# MotorControl.net
KiCad netlist of a schematic drawn in EAGLE
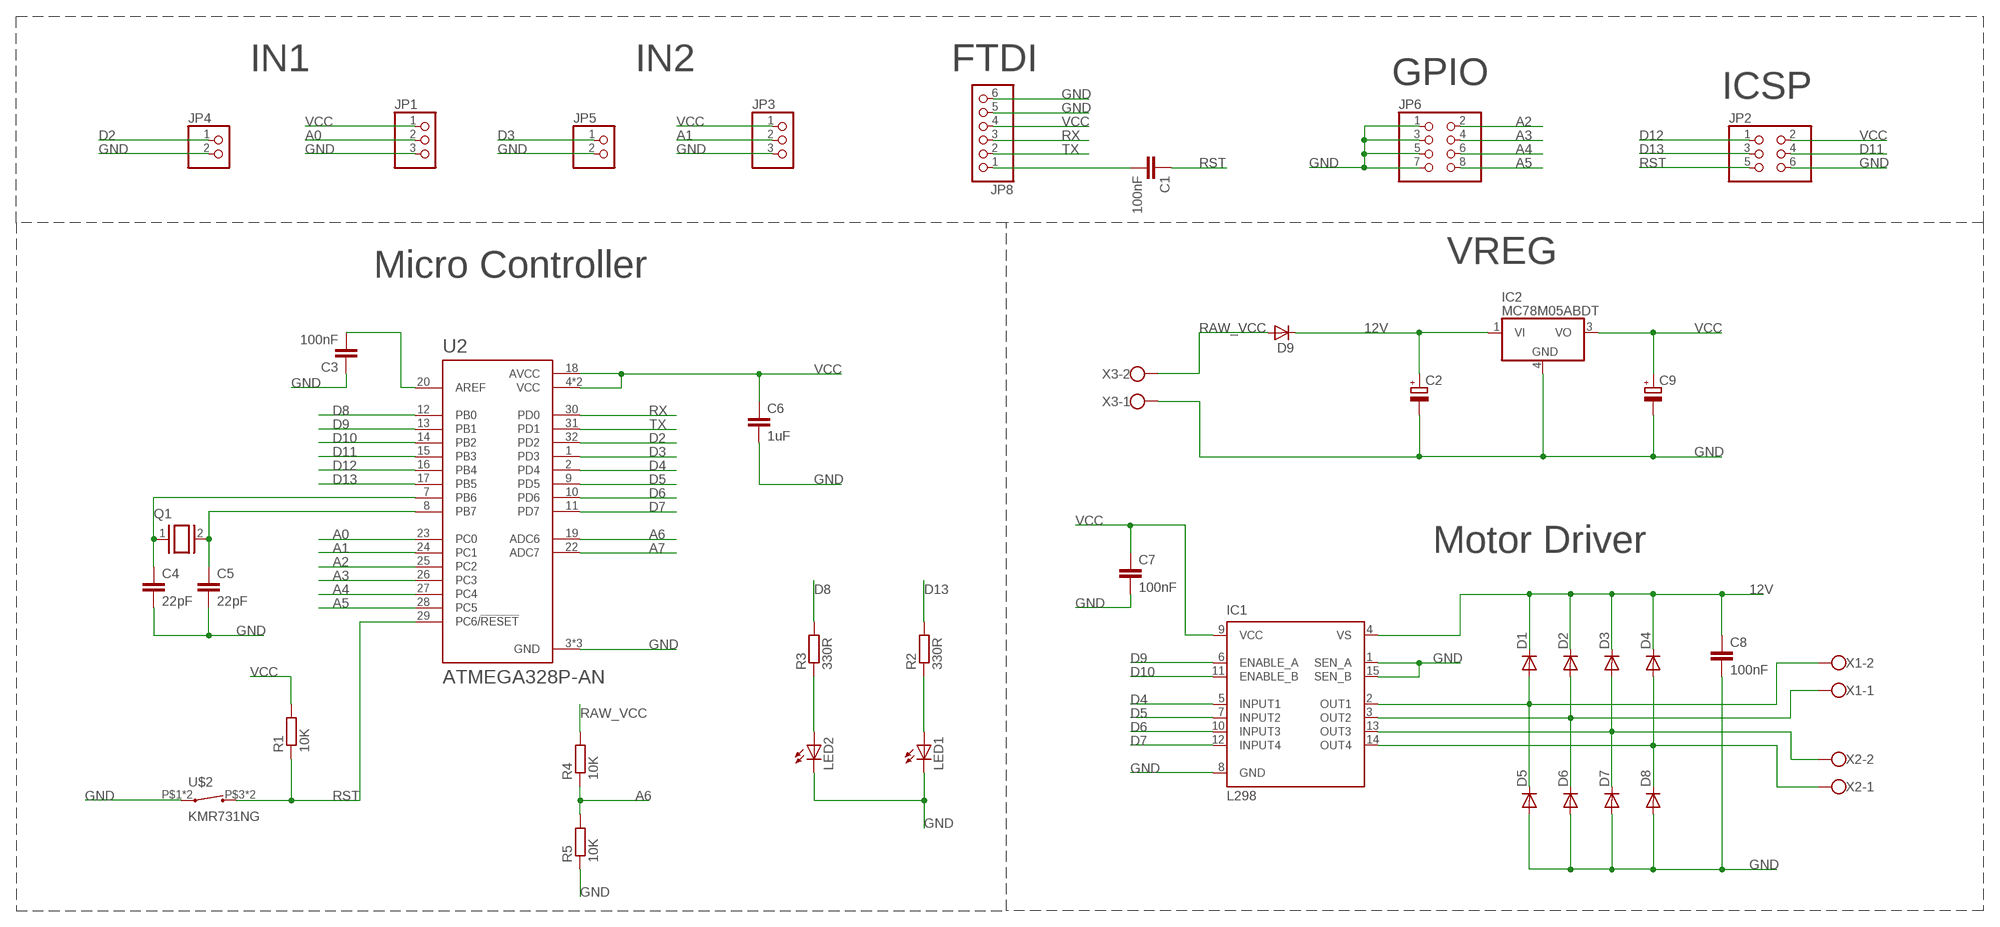
[diagram p0: schematic, sheet 1]

(export (version "E")
  (design (tool "Eeschema 10.0.6"))
  (components
    (comp (ref "C1")
      (value "100nF")
      (footprint "eagle-import:C1206")
      (libsource (lib "eagle-import") (part "CC1206"))
    )
    (comp (ref "C2")
      (value "CPOL-EU140CLH-0810")
      (footprint "eagle-import:140CLH-0810")
      (libsource (lib "eagle-import") (part "CPOL-EU140CLH-0810"))
    )
    (comp (ref "C3")
      (value "100nF")
      (footprint "eagle-import:C1206")
      (libsource (lib "eagle-import") (part "CC1206"))
    )
    (comp (ref "C4")
      (value "22pF")
      (footprint "eagle-import:C1206")
      (libsource (lib "eagle-import") (part "CC1206"))
    )
    (comp (ref "C5")
      (value "22pF")
      (footprint "eagle-import:C1206")
      (libsource (lib "eagle-import") (part "CC1206"))
    )
    (comp (ref "C6")
      (value "1uF")
      (footprint "eagle-import:C1206")
      (libsource (lib "eagle-import") (part "CC1206"))
    )
    (comp (ref "C7")
      (value "100nF")
      (footprint "eagle-import:C1206")
      (libsource (lib "eagle-import") (part "CC1206"))
    )
    (comp (ref "C8")
      (value "100nF")
      (footprint "eagle-import:C1206")
      (libsource (lib "eagle-import") (part "CC1206"))
    )
    (comp (ref "C9")
      (value "CPOL-EU140CLH-0810")
      (footprint "eagle-import:140CLH-0810")
      (libsource (lib "eagle-import") (part "CPOL-EU140CLH-0810"))
    )
    (comp (ref "D1")
      (value "DIODE-DO214AC")
      (footprint "eagle-import:DO214AC")
      (libsource (lib "eagle-import") (part "DIODE-DO214AC"))
    )
    (comp (ref "D2")
      (value "DIODE-DO214AC")
      (footprint "eagle-import:DO214AC")
      (libsource (lib "eagle-import") (part "DIODE-DO214AC"))
    )
    (comp (ref "D3")
      (value "DIODE-DO214AC")
      (footprint "eagle-import:DO214AC")
      (libsource (lib "eagle-import") (part "DIODE-DO214AC"))
    )
    (comp (ref "D4")
      (value "DIODE-DO214AC")
      (footprint "eagle-import:DO214AC")
      (libsource (lib "eagle-import") (part "DIODE-DO214AC"))
    )
    (comp (ref "D5")
      (value "DIODE-DO214AC")
      (footprint "eagle-import:DO214AC")
      (libsource (lib "eagle-import") (part "DIODE-DO214AC"))
    )
    (comp (ref "D6")
      (value "DIODE-DO214AC")
      (footprint "eagle-import:DO214AC")
      (libsource (lib "eagle-import") (part "DIODE-DO214AC"))
    )
    (comp (ref "D7")
      (value "DIODE-DO214AC")
      (footprint "eagle-import:DO214AC")
      (libsource (lib "eagle-import") (part "DIODE-DO214AC"))
    )
    (comp (ref "D8")
      (value "DIODE-DO214AC")
      (footprint "eagle-import:DO214AC")
      (libsource (lib "eagle-import") (part "DIODE-DO214AC"))
    )
    (comp (ref "D9")
      (value "DIODE_E-SMC")
      (footprint "eagle-import:DIODE_SMC")
      (libsource (lib "eagle-import") (part "DIODE_E-SMC"))
    )
    (comp (ref "IC1")
      (value "L298")
      (footprint "eagle-import:MULTIWATT-15")
      (fields (field (name "MPN") "L298N"))
      (libsource (lib "eagle-import") (part "L298"))
    )
    (comp (ref "IC2")
      (value "MC78M05ABDT")
      (footprint "eagle-import:DPACK_3")
      (libsource (lib "eagle-import") (part "MC78M05ABDT"))
    )
    (comp (ref "JP1")
      (value "PINHD-1X3")
      (footprint "eagle-import:1X03")
      (libsource (lib "eagle-import") (part "PINHD-1X3"))
    )
    (comp (ref "JP2")
      (value "PINHD-2X3")
      (footprint "eagle-import:2X03")
      (libsource (lib "eagle-import") (part "PINHD-2X3"))
    )
    (comp (ref "JP3")
      (value "PINHD-1X3")
      (footprint "eagle-import:1X03")
      (libsource (lib "eagle-import") (part "PINHD-1X3"))
    )
    (comp (ref "JP4")
      (value "PINHD-1X2")
      (footprint "eagle-import:1X02")
      (libsource (lib "eagle-import") (part "PINHD-1X2"))
    )
    (comp (ref "JP5")
      (value "PINHD-1X2")
      (footprint "eagle-import:1X02")
      (libsource (lib "eagle-import") (part "PINHD-1X2"))
    )
    (comp (ref "JP6")
      (value "PINHD-2X4")
      (footprint "eagle-import:2X04")
      (libsource (lib "eagle-import") (part "PINHD-2X4"))
    )
    (comp (ref "JP8")
      (value "PINHD-1X6")
      (footprint "eagle-import:1X06")
      (libsource (lib "eagle-import") (part "PINHD-1X6"))
    )
    (comp (ref "LED1")
      (value "LED_ESML0603")
      (footprint "eagle-import:LED_SML0603")
      (libsource (lib "eagle-import") (part "LED_ESML0603"))
    )
    (comp (ref "LED2")
      (value "LED3MM")
      (footprint "eagle-import:LED3MM")
      (libsource (lib "eagle-import") (part "LED3MM"))
    )
    (comp (ref "Q1")
      (value "XTAL/S")
      (footprint "eagle-import:QS")
      (libsource (lib "eagle-import") (part "XTAL/S"))
    )
    (comp (ref "R1")
      (value "10K")
      (footprint "eagle-import:R2012")
      (libsource (lib "eagle-import") (part "RR2012"))
    )
    (comp (ref "R2")
      (value "330R")
      (footprint "eagle-import:R2012")
      (libsource (lib "eagle-import") (part "RR2012"))
    )
    (comp (ref "R3")
      (value "330R")
      (footprint "eagle-import:R2012")
      (libsource (lib "eagle-import") (part "RR2012"))
    )
    (comp (ref "R4")
      (value "10K")
      (footprint "eagle-import:R2012")
      (libsource (lib "eagle-import") (part "RR2012"))
    )
    (comp (ref "R5")
      (value "10K")
      (footprint "eagle-import:R2012")
      (libsource (lib "eagle-import") (part "RR2012"))
    )
    (comp (ref "U$2")
      (value "KMR731NG")
      (footprint "eagle-import:KMR731NG")
      (libsource (lib "eagle-import") (part "KMR731NG"))
    )
    (comp (ref "U2")
      (value "ATMEGA328P-AN")
      (footprint "eagle-import:QFP80P900X900X120-32N")
      (fields (field (name "MF") "Microchip"))
      (libsource (lib "eagle-import") (part "ATMEGA328P-AN"))
    )
    (comp (ref "X1")
      (value "W237-102")
      (footprint "eagle-import:W237-102")
      (fields (field (name "MPN") "237-102"))
      (libsource (lib "eagle-import") (part "W237-102"))
    )
    (comp (ref "X2")
      (value "W237-102")
      (footprint "eagle-import:W237-102")
      (fields (field (name "MPN") "237-102"))
      (libsource (lib "eagle-import") (part "W237-102"))
    )
    (comp (ref "X3")
      (value "W237-102")
      (footprint "eagle-import:W237-102")
      (fields (field (name "MPN") "237-102"))
      (libsource (lib "eagle-import") (part "W237-102"))
    )
  )
  (nets
    (net (code "1") (name "/12V") (class "Default")
      (node (ref "C2") (pin "+") (pinfunction "+_+") (pintype "passive"))
      (node (ref "C8") (pin "1") (pinfunction "1_1") (pintype "passive"))
      (node (ref "D1") (pin "C") (pinfunction "C_C") (pintype "passive"))
      (node (ref "D2") (pin "C") (pinfunction "C_C") (pintype "passive"))
      (node (ref "D3") (pin "C") (pinfunction "C_C") (pintype "passive"))
      (node (ref "D4") (pin "C") (pinfunction "C_C") (pintype "passive"))
      (node (ref "D9") (pin "C") (pinfunction "A_C") (pintype "passive"))
      (node (ref "IC1") (pin "4") (pinfunction "VS_4") (pintype "power_in"))
      (node (ref "IC2") (pin "1") (pinfunction "VI_1") (pintype "input"))
    )
    (net (code "2") (name "/A0") (class "Default")
      (node (ref "JP1") (pin "2") (pinfunction "2_2") (pintype "passive"))
      (node (ref "U2") (pin "23") (pinfunction "PC0_23") (pintype "bidirectional"))
    )
    (net (code "3") (name "/A1") (class "Default")
      (node (ref "JP3") (pin "2") (pinfunction "2_2") (pintype "passive"))
      (node (ref "U2") (pin "24") (pinfunction "PC1_24") (pintype "bidirectional"))
    )
    (net (code "4") (name "/A2") (class "Default")
      (node (ref "JP6") (pin "2") (pinfunction "2_2") (pintype "passive"))
      (node (ref "U2") (pin "25") (pinfunction "PC2_25") (pintype "bidirectional"))
    )
    (net (code "5") (name "/A3") (class "Default")
      (node (ref "JP6") (pin "4") (pinfunction "4_4") (pintype "passive"))
      (node (ref "U2") (pin "26") (pinfunction "PC3_26") (pintype "bidirectional"))
    )
    (net (code "6") (name "/A4") (class "Default")
      (node (ref "JP6") (pin "6") (pinfunction "6_6") (pintype "passive"))
      (node (ref "U2") (pin "27") (pinfunction "PC4_27") (pintype "bidirectional"))
    )
    (net (code "7") (name "/A5") (class "Default")
      (node (ref "JP6") (pin "8") (pinfunction "8_8") (pintype "passive"))
      (node (ref "U2") (pin "28") (pinfunction "PC5_28") (pintype "bidirectional"))
    )
    (net (code "8") (name "/A6") (class "Default")
      (node (ref "R4") (pin "1") (pinfunction "1_1") (pintype "passive"))
      (node (ref "R5") (pin "2") (pinfunction "2_2") (pintype "passive"))
      (node (ref "U2") (pin "19") (pinfunction "ADC6_19") (pintype "bidirectional"))
    )
    (net (code "9") (name "/A7") (class "Default")
      (node (ref "U2") (pin "22") (pinfunction "ADC7_22") (pintype "bidirectional"))
    )
    (net (code "10") (name "/D2") (class "Default")
      (node (ref "JP4") (pin "1") (pinfunction "1_1") (pintype "passive"))
      (node (ref "U2") (pin "32") (pinfunction "PD2_32") (pintype "bidirectional"))
    )
    (net (code "11") (name "/D3") (class "Default")
      (node (ref "JP5") (pin "1") (pinfunction "1_1") (pintype "passive"))
      (node (ref "U2") (pin "1") (pinfunction "PD3_1") (pintype "bidirectional"))
    )
    (net (code "12") (name "/D4") (class "Default")
      (node (ref "IC1") (pin "5") (pinfunction "INPUT1_5") (pintype "input"))
      (node (ref "U2") (pin "2") (pinfunction "PD4_2") (pintype "bidirectional"))
    )
    (net (code "13") (name "/D5") (class "Default")
      (node (ref "IC1") (pin "7") (pinfunction "INPUT2_7") (pintype "input"))
      (node (ref "U2") (pin "9") (pinfunction "PD5_9") (pintype "bidirectional"))
    )
    (net (code "14") (name "/D6") (class "Default")
      (node (ref "IC1") (pin "10") (pinfunction "INPUT3_10") (pintype "input"))
      (node (ref "U2") (pin "10") (pinfunction "PD6_10") (pintype "bidirectional"))
    )
    (net (code "15") (name "/D7") (class "Default")
      (node (ref "IC1") (pin "12") (pinfunction "INPUT4_12") (pintype "input"))
      (node (ref "U2") (pin "11") (pinfunction "PD7_11") (pintype "bidirectional"))
    )
    (net (code "16") (name "/D8") (class "Default")
      (node (ref "R3") (pin "2") (pinfunction "2_2") (pintype "passive"))
      (node (ref "U2") (pin "12") (pinfunction "PB0_12") (pintype "bidirectional"))
    )
    (net (code "17") (name "/D9") (class "Default")
      (node (ref "IC1") (pin "6") (pinfunction "ENABLE_A_6") (pintype "input"))
      (node (ref "U2") (pin "13") (pinfunction "PB1_13") (pintype "bidirectional"))
    )
    (net (code "18") (name "/D10") (class "Default")
      (node (ref "IC1") (pin "11") (pinfunction "ENABLE_B_11") (pintype "input"))
      (node (ref "U2") (pin "14") (pinfunction "PB2_14") (pintype "bidirectional"))
    )
    (net (code "19") (name "/D11") (class "Default")
      (node (ref "JP2") (pin "4") (pinfunction "4_4") (pintype "passive"))
      (node (ref "U2") (pin "15") (pinfunction "PB3_15") (pintype "bidirectional"))
    )
    (net (code "20") (name "/D12") (class "Default")
      (node (ref "JP2") (pin "1") (pinfunction "1_1") (pintype "passive"))
      (node (ref "U2") (pin "16") (pinfunction "PB4_16") (pintype "bidirectional"))
    )
    (net (code "21") (name "/D13") (class "Default")
      (node (ref "JP2") (pin "3") (pinfunction "3_3") (pintype "passive"))
      (node (ref "R2") (pin "2") (pinfunction "2_2") (pintype "passive"))
      (node (ref "U2") (pin "17") (pinfunction "PB5_17") (pintype "bidirectional"))
    )
    (net (code "22") (name "/GND") (class "Default")
      (node (ref "C2") (pin "-") (pinfunction "-_-") (pintype "passive"))
      (node (ref "C3") (pin "1") (pinfunction "1_1") (pintype "passive"))
      (node (ref "C4") (pin "2") (pinfunction "2_2") (pintype "passive"))
      (node (ref "C5") (pin "2") (pinfunction "2_2") (pintype "passive"))
      (node (ref "C6") (pin "2") (pinfunction "2_2") (pintype "passive"))
      (node (ref "C7") (pin "2") (pinfunction "2_2") (pintype "passive"))
      (node (ref "C8") (pin "2") (pinfunction "2_2") (pintype "passive"))
      (node (ref "C9") (pin "-") (pinfunction "-_-") (pintype "passive"))
      (node (ref "D5") (pin "A") (pinfunction "A_A") (pintype "passive"))
      (node (ref "D6") (pin "A") (pinfunction "A_A") (pintype "passive"))
      (node (ref "D7") (pin "A") (pinfunction "A_A") (pintype "passive"))
      (node (ref "D8") (pin "A") (pinfunction "A_A") (pintype "passive"))
      (node (ref "IC1") (pin "1") (pinfunction "SEN_A_1") (pintype "input"))
      (node (ref "IC1") (pin "15") (pinfunction "SEN_B_15") (pintype "input"))
      (node (ref "IC1") (pin "8") (pinfunction "GND_8") (pintype "power_in"))
      (node (ref "IC2") (pin "4") (pinfunction "GND_4") (pintype "passive"))
      (node (ref "JP1") (pin "3") (pinfunction "3_3") (pintype "passive"))
      (node (ref "JP2") (pin "6") (pinfunction "6_6") (pintype "passive"))
      (node (ref "JP3") (pin "3") (pinfunction "3_3") (pintype "passive"))
      (node (ref "JP4") (pin "2") (pinfunction "2_2") (pintype "passive"))
      (node (ref "JP5") (pin "2") (pinfunction "2_2") (pintype "passive"))
      (node (ref "JP6") (pin "1") (pinfunction "1_1") (pintype "passive"))
      (node (ref "JP6") (pin "3") (pinfunction "3_3") (pintype "passive"))
      (node (ref "JP6") (pin "5") (pinfunction "5_5") (pintype "passive"))
      (node (ref "JP6") (pin "7") (pinfunction "7_7") (pintype "passive"))
      (node (ref "JP8") (pin "5") (pinfunction "5_5") (pintype "passive"))
      (node (ref "JP8") (pin "6") (pinfunction "6_6") (pintype "passive"))
      (node (ref "LED1") (pin "C") (pinfunction "C_C") (pintype "passive"))
      (node (ref "LED2") (pin "K") (pinfunction "C_K") (pintype "passive"))
      (node (ref "R5") (pin "1") (pinfunction "1_1") (pintype "passive"))
      (node (ref "U$2") (pin "P$1") (pinfunction "1_P$1") (pintype "passive"))
      (node (ref "U$2") (pin "P$2") (pinfunction "1_P$2") (pintype "passive"))
      (node (ref "U2") (pin "21") (pinfunction "GND_21") (pintype "power_in"))
      (node (ref "U2") (pin "3") (pinfunction "GND_3") (pintype "power_in"))
      (node (ref "U2") (pin "5") (pinfunction "GND_5") (pintype "power_in"))
      (node (ref "X3") (pin "1") (pinfunction "KL_1") (pintype "passive"))
    )
    (net (code "23") (name "/RAW_VCC") (class "Default")
      (node (ref "D9") (pin "A") (pinfunction "C_A") (pintype "passive"))
      (node (ref "R4") (pin "2") (pinfunction "2_2") (pintype "passive"))
      (node (ref "X3") (pin "2") (pinfunction "KL_2") (pintype "passive"))
    )
    (net (code "24") (name "/RST") (class "Default")
      (node (ref "C1") (pin "1") (pinfunction "1_1") (pintype "passive"))
      (node (ref "JP2") (pin "5") (pinfunction "5_5") (pintype "passive"))
      (node (ref "R1") (pin "1") (pinfunction "1_1") (pintype "passive"))
      (node (ref "U$2") (pin "P$3") (pinfunction "2_P$3") (pintype "passive"))
      (node (ref "U$2") (pin "P$4") (pinfunction "2_P$4") (pintype "passive"))
      (node (ref "U2") (pin "29") (pinfunction "PC6/~{RESET}_29") (pintype "bidirectional"))
    )
    (net (code "25") (name "/RX") (class "Default")
      (node (ref "JP8") (pin "3") (pinfunction "3_3") (pintype "passive"))
      (node (ref "U2") (pin "30") (pinfunction "PD0_30") (pintype "bidirectional"))
    )
    (net (code "26") (name "/TX") (class "Default")
      (node (ref "JP8") (pin "2") (pinfunction "2_2") (pintype "passive"))
      (node (ref "U2") (pin "31") (pinfunction "PD1_31") (pintype "bidirectional"))
    )
    (net (code "27") (name "/VCC") (class "Default")
      (node (ref "C6") (pin "1") (pinfunction "1_1") (pintype "passive"))
      (node (ref "C7") (pin "1") (pinfunction "1_1") (pintype "passive"))
      (node (ref "C9") (pin "+") (pinfunction "+_+") (pintype "passive"))
      (node (ref "IC1") (pin "9") (pinfunction "VCC_9") (pintype "power_in"))
      (node (ref "IC2") (pin "3") (pinfunction "VO_3") (pintype "passive"))
      (node (ref "JP1") (pin "1") (pinfunction "1_1") (pintype "passive"))
      (node (ref "JP2") (pin "2") (pinfunction "2_2") (pintype "passive"))
      (node (ref "JP3") (pin "1") (pinfunction "1_1") (pintype "passive"))
      (node (ref "JP8") (pin "4") (pinfunction "4_4") (pintype "passive"))
      (node (ref "R1") (pin "2") (pinfunction "2_2") (pintype "passive"))
      (node (ref "U2") (pin "18") (pinfunction "AVCC_18") (pintype "power_in"))
      (node (ref "U2") (pin "4") (pinfunction "VCC_4") (pintype "power_in"))
      (node (ref "U2") (pin "6") (pinfunction "VCC_6") (pintype "power_in"))
    )
    (net (code "28") (name "Net-(C1-Pad2)") (class "Default")
      (node (ref "C1") (pin "2") (pinfunction "2_2") (pintype "passive"))
      (node (ref "JP8") (pin "1") (pinfunction "1_1") (pintype "passive"))
    )
    (net (code "29") (name "Net-(IC1-OUT1)") (class "Default")
      (node (ref "D1") (pin "A") (pinfunction "A_A") (pintype "passive"))
      (node (ref "D5") (pin "C") (pinfunction "C_C") (pintype "passive"))
      (node (ref "IC1") (pin "2") (pinfunction "OUT1_2") (pintype "output"))
      (node (ref "X1") (pin "2") (pinfunction "KL_2") (pintype "passive"))
    )
    (net (code "30") (name "Net-(IC1-OUT2)") (class "Default")
      (node (ref "D2") (pin "A") (pinfunction "A_A") (pintype "passive"))
      (node (ref "D6") (pin "C") (pinfunction "C_C") (pintype "passive"))
      (node (ref "IC1") (pin "3") (pinfunction "OUT2_3") (pintype "output"))
      (node (ref "X1") (pin "1") (pinfunction "KL_1") (pintype "passive"))
    )
    (net (code "31") (name "Net-(IC1-OUT3)") (class "Default")
      (node (ref "D3") (pin "A") (pinfunction "A_A") (pintype "passive"))
      (node (ref "D7") (pin "C") (pinfunction "C_C") (pintype "passive"))
      (node (ref "IC1") (pin "13") (pinfunction "OUT3_13") (pintype "output"))
      (node (ref "X2") (pin "2") (pinfunction "KL_2") (pintype "passive"))
    )
    (net (code "32") (name "Net-(IC1-OUT4)") (class "Default")
      (node (ref "D4") (pin "A") (pinfunction "A_A") (pintype "passive"))
      (node (ref "D8") (pin "C") (pinfunction "C_C") (pintype "passive"))
      (node (ref "IC1") (pin "14") (pinfunction "OUT4_14") (pintype "output"))
      (node (ref "X2") (pin "1") (pinfunction "KL_1") (pintype "passive"))
    )
    (net (code "33") (name "Net-(LED1-PadA)") (class "Default")
      (node (ref "LED1") (pin "A") (pinfunction "A_A") (pintype "passive"))
      (node (ref "R2") (pin "1") (pinfunction "1_1") (pintype "passive"))
    )
    (net (code "34") (name "Net-(LED2-PadA)") (class "Default")
      (node (ref "LED2") (pin "A") (pinfunction "A_A") (pintype "passive"))
      (node (ref "R3") (pin "1") (pinfunction "1_1") (pintype "passive"))
    )
    (net (code "35") (name "Net-(U2-AREF)") (class "Default")
      (node (ref "C3") (pin "2") (pinfunction "2_2") (pintype "passive"))
      (node (ref "U2") (pin "20") (pinfunction "AREF_20") (pintype "input"))
    )
    (net (code "36") (name "Net-(U2-PB6)") (class "Default")
      (node (ref "C4") (pin "1") (pinfunction "1_1") (pintype "passive"))
      (node (ref "Q1") (pin "1") (pinfunction "1_1") (pintype "passive"))
      (node (ref "U2") (pin "7") (pinfunction "PB6_7") (pintype "bidirectional"))
    )
    (net (code "37") (name "Net-(U2-PB7)") (class "Default")
      (node (ref "C5") (pin "1") (pinfunction "1_1") (pintype "passive"))
      (node (ref "Q1") (pin "2") (pinfunction "2_2") (pintype "passive"))
      (node (ref "U2") (pin "8") (pinfunction "PB7_8") (pintype "bidirectional"))
    )
  )
)
